# Controller.net
KiCad netlist of a schematic drawn in EAGLE
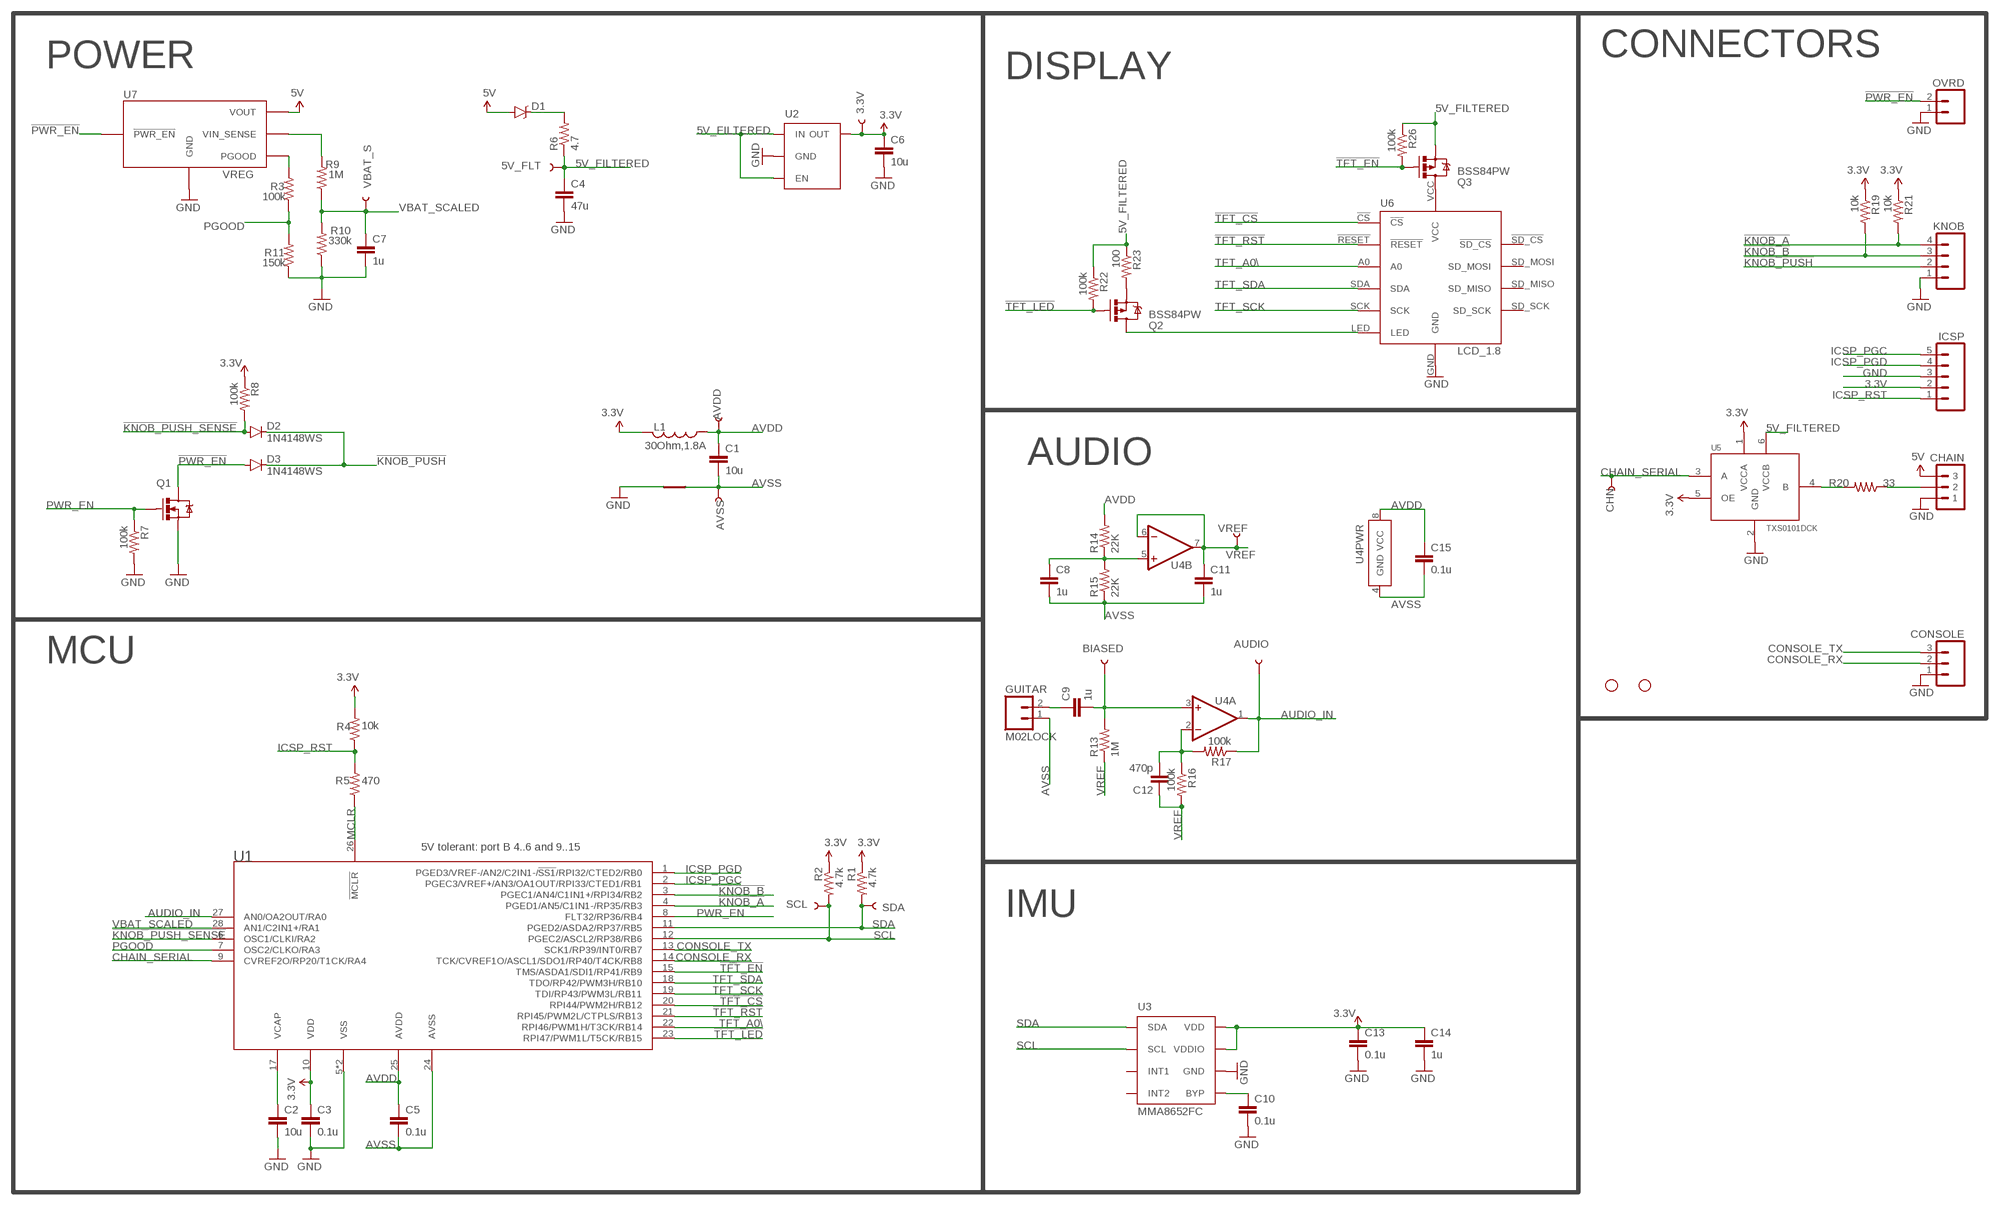
[diagram p0: schematic, sheet 1]

(export (version "E")
  (design (tool "Eeschema 10.0.6"))
  (components
    (comp (ref "3.3V")
      (value "TEST-POINT3")
      (footprint "eagle-import:PAD.03X.03")
      (libsource (lib "eagle-import") (part "TEST-POINT3"))
    )
    (comp (ref "5V_FLT")
      (value "TEST-POINT3")
      (footprint "eagle-import:PAD.03X.03")
      (libsource (lib "eagle-import") (part "TEST-POINT3"))
    )
    (comp (ref "AUDIO")
      (value "TEST-POINT3")
      (footprint "eagle-import:PAD.03X.03")
      (libsource (lib "eagle-import") (part "TEST-POINT3"))
    )
    (comp (ref "AVDD")
      (value "TEST-POINT3")
      (footprint "eagle-import:PAD.03X.03")
      (libsource (lib "eagle-import") (part "TEST-POINT3"))
    )
    (comp (ref "AVSS")
      (value "TEST-POINT3")
      (footprint "eagle-import:PAD.03X.03")
      (libsource (lib "eagle-import") (part "TEST-POINT3"))
    )
    (comp (ref "BIASED")
      (value "TEST-POINT3")
      (footprint "eagle-import:PAD.03X.03")
      (libsource (lib "eagle-import") (part "TEST-POINT3"))
    )
    (comp (ref "C1")
      (value "10u")
      (footprint "eagle-import:0805")
      (libsource (lib "eagle-import") (part "CAP0805"))
    )
    (comp (ref "C2")
      (value "10u")
      (footprint "eagle-import:0805")
      (libsource (lib "eagle-import") (part "CAP0805"))
    )
    (comp (ref "C3")
      (value "0.1u")
      (footprint "eagle-import:0603-CAP")
      (libsource (lib "eagle-import") (part "CAP0603-CAP"))
    )
    (comp (ref "C4")
      (value "47u")
      (footprint "eagle-import:1206")
      (libsource (lib "eagle-import") (part "CAP1206"))
    )
    (comp (ref "C5")
      (value "0.1u")
      (footprint "eagle-import:0603-CAP")
      (libsource (lib "eagle-import") (part "CAP0603-CAP"))
    )
    (comp (ref "C6")
      (value "10u")
      (footprint "eagle-import:0603-CAP")
      (libsource (lib "eagle-import") (part "10UF-6.3V-20%(0603)"))
    )
    (comp (ref "C7")
      (value "1u")
      (footprint "eagle-import:0603-CAP")
      (libsource (lib "eagle-import") (part "CAP0603-CAP"))
    )
    (comp (ref "C8")
      (value "1u")
      (footprint "eagle-import:0603-CAP")
      (libsource (lib "eagle-import") (part "CAP0603-CAP"))
    )
    (comp (ref "C9")
      (value "1u")
      (footprint "eagle-import:0603-CAP")
      (libsource (lib "eagle-import") (part "CAP0603-CAP"))
    )
    (comp (ref "C10")
      (value "0.1u")
      (footprint "eagle-import:0603-CAP")
      (libsource (lib "eagle-import") (part "CAP0603-CAP"))
    )
    (comp (ref "C11")
      (value "1u")
      (footprint "eagle-import:0603-CAP")
      (libsource (lib "eagle-import") (part "CAP0603-CAP"))
    )
    (comp (ref "C12")
      (value "470p")
      (footprint "eagle-import:0603-CAP")
      (libsource (lib "eagle-import") (part "CAP0603-CAP"))
    )
    (comp (ref "C13")
      (value "0.1u")
      (footprint "eagle-import:0603-CAP")
      (libsource (lib "eagle-import") (part "CAP0603-CAP"))
    )
    (comp (ref "C14")
      (value "1u")
      (footprint "eagle-import:0603-CAP")
      (libsource (lib "eagle-import") (part "CAP0603-CAP"))
    )
    (comp (ref "C15")
      (value "0.1u")
      (footprint "eagle-import:0603-CAP")
      (libsource (lib "eagle-import") (part "CAP0603-CAP"))
    )
    (comp (ref "CHAIN")
      (value "M030.1PWR+SIG")
      (footprint "eagle-import:1X03-0.1PWR+SIG")
      (libsource (lib "eagle-import") (part "M030.1PWR+SIG"))
    )
    (comp (ref "CHN")
      (value "TEST-POINT3")
      (footprint "eagle-import:PAD.03X.03")
      (libsource (lib "eagle-import") (part "TEST-POINT3"))
    )
    (comp (ref "CONSOLE")
      (value "M03LOCK")
      (footprint "eagle-import:1X03_LOCK")
      (libsource (lib "eagle-import") (part "SparkFun-Connectors_M03LOCK"))
    )
    (comp (ref "D1")
      (value "DB2J20900L")
      (footprint "eagle-import:SOD-323")
      (libsource (lib "eagle-import") (part "DIODE-SCHOTTKY-PMEG4005EJ"))
    )
    (comp (ref "D2")
      (value "1N4148WS")
      (footprint "eagle-import:SOD-323")
      (libsource (lib "eagle-import") (part "1N4148WS"))
    )
    (comp (ref "D3")
      (value "1N4148WS")
      (footprint "eagle-import:SOD-323")
      (libsource (lib "eagle-import") (part "1N4148WS"))
    )
    (comp (ref "GUITAR")
      (value "M02LOCK")
      (footprint "eagle-import:1X02_LOCK")
      (libsource (lib "eagle-import") (part "M02LOCK"))
    )
    (comp (ref "ICSP")
      (value "M05LOCK")
      (footprint "eagle-import:1X05_LOCK")
      (libsource (lib "eagle-import") (part "M05LOCK"))
    )
    (comp (ref "JP1")
      (value "STAND-OFF")
      (footprint "eagle-import:STAND-OFF")
      (libsource (lib "eagle-import") (part "STAND-OFF"))
    )
    (comp (ref "JP2")
      (value "STAND-OFF")
      (footprint "eagle-import:STAND-OFF")
      (libsource (lib "eagle-import") (part "STAND-OFF"))
    )
    (comp (ref "KNOB")
      (value "M04LOCK")
      (footprint "eagle-import:1X04_LOCK")
      (libsource (lib "eagle-import") (part "M04LOCK"))
    )
    (comp (ref "L1")
      (value "30Ohm,1.8A")
      (footprint "eagle-import:0603")
      (libsource (lib "eagle-import") (part "INDUCTOR0603"))
    )
    (comp (ref "OVRD")
      (value "M02LOCK")
      (footprint "eagle-import:1X02_LOCK")
      (libsource (lib "eagle-import") (part "M02LOCK"))
    )
    (comp (ref "Q1")
      (value "MOSFET-NCHANNEL2N7002PW")
      (footprint "eagle-import:SOT323")
      (libsource (lib "eagle-import") (part "MOSFET-NCHANNEL2N7002PW"))
    )
    (comp (ref "Q2")
      (value "BSS84PW")
      (footprint "eagle-import:SOT323")
      (libsource (lib "eagle-import") (part "BSS84PW"))
    )
    (comp (ref "Q3")
      (value "BSS84PW")
      (footprint "eagle-import:SOT323")
      (libsource (lib "eagle-import") (part "BSS84PW"))
    )
    (comp (ref "R1")
      (value "4.7k")
      (footprint "eagle-import:0603-RES")
      (libsource (lib "eagle-import") (part "RESISTOR0603"))
    )
    (comp (ref "R2")
      (value "4.7k")
      (footprint "eagle-import:0603-RES")
      (libsource (lib "eagle-import") (part "RESISTOR0603"))
    )
    (comp (ref "R3")
      (value "100k")
      (footprint "eagle-import:0603-RES")
      (libsource (lib "eagle-import") (part "RESISTOR0603"))
    )
    (comp (ref "R4")
      (value "10k")
      (footprint "eagle-import:0603-RES")
      (libsource (lib "eagle-import") (part "RESISTOR0603"))
    )
    (comp (ref "R5")
      (value "470")
      (footprint "eagle-import:0603-RES")
      (libsource (lib "eagle-import") (part "RESISTOR0603"))
    )
    (comp (ref "R6")
      (value "4.7")
      (footprint "eagle-import:0603-RES")
      (libsource (lib "eagle-import") (part "RESISTOR0603"))
    )
    (comp (ref "R7")
      (value "100k")
      (footprint "eagle-import:0603-RES")
      (libsource (lib "eagle-import") (part "RESISTOR0603"))
    )
    (comp (ref "R8")
      (value "100k")
      (footprint "eagle-import:0603-RES")
      (libsource (lib "eagle-import") (part "RESISTOR0603"))
    )
    (comp (ref "R9")
      (value "1M")
      (footprint "eagle-import:0603-RES")
      (libsource (lib "eagle-import") (part "RESISTOR0603"))
    )
    (comp (ref "R10")
      (value "330k")
      (footprint "eagle-import:0603-RES")
      (libsource (lib "eagle-import") (part "RESISTOR0603"))
    )
    (comp (ref "R11")
      (value "150k")
      (footprint "eagle-import:0603-RES")
      (libsource (lib "eagle-import") (part "RESISTOR0603"))
    )
    (comp (ref "R13")
      (value "1M")
      (footprint "eagle-import:0603-RES")
      (libsource (lib "eagle-import") (part "RESISTOR0603"))
    )
    (comp (ref "R14")
      (value "22K")
      (footprint "eagle-import:0603-RES")
      (libsource (lib "eagle-import") (part "RESISTOR0603"))
    )
    (comp (ref "R15")
      (value "22K")
      (footprint "eagle-import:0603-RES")
      (libsource (lib "eagle-import") (part "RESISTOR0603"))
    )
    (comp (ref "R16")
      (value "100k")
      (footprint "eagle-import:0603-RES")
      (libsource (lib "eagle-import") (part "RESISTOR0603"))
    )
    (comp (ref "R17")
      (value "100k")
      (footprint "eagle-import:0603-RES")
      (libsource (lib "eagle-import") (part "RESISTOR0603"))
    )
    (comp (ref "R19")
      (value "10k")
      (footprint "eagle-import:0603-RES")
      (libsource (lib "eagle-import") (part "RESISTOR0603"))
    )
    (comp (ref "R20")
      (value "33")
      (footprint "eagle-import:0603-RES")
      (libsource (lib "eagle-import") (part "RESISTOR0603"))
    )
    (comp (ref "R21")
      (value "10k")
      (footprint "eagle-import:0603-RES")
      (libsource (lib "eagle-import") (part "RESISTOR0603"))
    )
    (comp (ref "R22")
      (value "100k")
      (footprint "eagle-import:0603-RES")
      (libsource (lib "eagle-import") (part "RESISTOR0603"))
    )
    (comp (ref "R23")
      (value "100")
      (footprint "eagle-import:0603-RES")
      (libsource (lib "eagle-import") (part "RESISTOR0603"))
    )
    (comp (ref "R26")
      (value "100k")
      (footprint "eagle-import:0603-RES")
      (libsource (lib "eagle-import") (part "RESISTOR0603"))
    )
    (comp (ref "SCL")
      (value "TEST-POINT3")
      (footprint "eagle-import:PAD.03X.03")
      (libsource (lib "eagle-import") (part "TEST-POINT3"))
    )
    (comp (ref "SDA")
      (value "TEST-POINT3")
      (footprint "eagle-import:PAD.03X.03")
      (libsource (lib "eagle-import") (part "TEST-POINT3"))
    )
    (comp (ref "SH1")
      (value "SHORT")
      (footprint "eagle-import:SHORT_TOP-8")
      (libsource (lib "eagle-import") (part "SHORT"))
    )
    (comp (ref "U1")
      (value "DSPIC33EPXXXMC202/502/PT")
      (footprint "eagle-import:QFN-S-28")
      (libsource (lib "eagle-import") (part "DSPIC33EPXXXMC202/502/PT"))
    )
    (comp (ref "U2")
      (value "MIC5365YC5")
      (footprint "eagle-import:SC70")
      (libsource (lib "eagle-import") (part "MIC5365YC5"))
    )
    (comp (ref "U3")
      (value "MMA8652FC")
      (footprint "eagle-import:10-VFDFN")
      (libsource (lib "eagle-import") (part "MMA8652FC"))
    )
    (comp (ref "U4")
      (value "MCP6002MS")
      (footprint "eagle-import:MSOP-8")
      (libsource (lib "eagle-import") (part "MCP6002MS"))
    )
    (comp (ref "U5")
      (value "TXS0101DCK")
      (footprint "eagle-import:SC70-6")
      (libsource (lib "eagle-import") (part "TXS0101DCK"))
    )
    (comp (ref "U6")
      (value "LCD_1.8")
      (footprint "eagle-import:LCD_1.8")
      (libsource (lib "eagle-import") (part "LCD_1.8"))
    )
    (comp (ref "U7")
      (value "VREG")
      (footprint "eagle-import:VREG")
      (libsource (lib "eagle-import") (part "VREG"))
    )
    (comp (ref "VBAT_S")
      (value "TEST-POINT3")
      (footprint "eagle-import:PAD.03X.03")
      (libsource (lib "eagle-import") (part "TEST-POINT3"))
    )
    (comp (ref "VREF")
      (value "TEST-POINT3")
      (footprint "eagle-import:PAD.03X.03")
      (libsource (lib "eagle-import") (part "TEST-POINT3"))
    )
  )
  (nets
    (net (code "1") (name "/5V_FILTERED") (class "Default")
      (node (ref "5V_FLT") (pin "P$1") (pinfunction "1_P$1") (pintype "bidirectional"))
      (node (ref "C4") (pin "1") (pinfunction "1_1") (pintype "passive"))
      (node (ref "Q3") (pin "2") (pinfunction "S_2") (pintype "passive"))
      (node (ref "R22") (pin "1") (pinfunction "1_1") (pintype "passive"))
      (node (ref "R23") (pin "1") (pinfunction "1_1") (pintype "passive"))
      (node (ref "R26") (pin "1") (pinfunction "1_1") (pintype "passive"))
      (node (ref "R6") (pin "1") (pinfunction "1_1") (pintype "passive"))
      (node (ref "U2") (pin "1") (pinfunction "IN_1") (pintype "power_in"))
      (node (ref "U2") (pin "3") (pinfunction "EN_3") (pintype "input"))
      (node (ref "U5") (pin "6") (pinfunction "VCCB_6") (pintype "bidirectional"))
    )
    (net (code "2") (name "/AUDIO_IN") (class "Default")
      (node (ref "AUDIO") (pin "P$1") (pinfunction "1_P$1") (pintype "bidirectional"))
      (node (ref "R17") (pin "1") (pinfunction "1_1") (pintype "passive"))
      (node (ref "U1") (pin "27") (pinfunction "AN0/OA2OUT/RA0_27") (pintype "bidirectional"))
      (node (ref "U4") (pin "1") (pinfunction "OUT_1") (pintype "output"))
    )
    (net (code "3") (name "/AVDD") (class "Default")
      (node (ref "AVDD") (pin "P$1") (pinfunction "1_P$1") (pintype "bidirectional"))
      (node (ref "C1") (pin "1") (pinfunction "1_1") (pintype "passive"))
      (node (ref "C15") (pin "1") (pinfunction "1_1") (pintype "passive"))
      (node (ref "C5") (pin "1") (pinfunction "1_1") (pintype "passive"))
      (node (ref "L1") (pin "1") (pinfunction "1_1") (pintype "passive"))
      (node (ref "R14") (pin "2") (pinfunction "2_2") (pintype "passive"))
      (node (ref "U1") (pin "25") (pinfunction "AVDD_25") (pintype "bidirectional"))
      (node (ref "U4") (pin "8") (pinfunction "VCC_8") (pintype "power_in"))
    )
    (net (code "4") (name "/AVSS") (class "Default")
      (node (ref "AVSS") (pin "P$1") (pinfunction "1_P$1") (pintype "bidirectional"))
      (node (ref "C1") (pin "2") (pinfunction "2_2") (pintype "passive"))
      (node (ref "C11") (pin "2") (pinfunction "2_2") (pintype "passive"))
      (node (ref "C15") (pin "2") (pinfunction "2_2") (pintype "passive"))
      (node (ref "C5") (pin "2") (pinfunction "2_2") (pintype "passive"))
      (node (ref "C8") (pin "2") (pinfunction "2_2") (pintype "passive"))
      (node (ref "GUITAR") (pin "1") (pinfunction "1_1") (pintype "passive"))
      (node (ref "R15") (pin "1") (pinfunction "1_1") (pintype "passive"))
      (node (ref "SH1") (pin "2") (pinfunction "P$2_2") (pintype "bidirectional"))
      (node (ref "U1") (pin "24") (pinfunction "AVSS_24") (pintype "bidirectional"))
      (node (ref "U4") (pin "4") (pinfunction "GND_4") (pintype "power_in"))
    )
    (net (code "5") (name "/CHAIN_SERIAL") (class "Default")
      (node (ref "CHN") (pin "P$1") (pinfunction "1_P$1") (pintype "bidirectional"))
      (node (ref "U1") (pin "9") (pinfunction "CVREF2O/RP20/T1CK/RA4_9") (pintype "bidirectional"))
      (node (ref "U5") (pin "3") (pinfunction "A_3") (pintype "bidirectional"))
    )
    (net (code "6") (name "/CONSOLE_RX") (class "Default")
      (node (ref "CONSOLE") (pin "2") (pinfunction "2_2") (pintype "passive"))
      (node (ref "U1") (pin "14") (pinfunction "TCK/CVREF1O/ASCL1/SDO1/RP40/T4CK/RB8_14") (pintype "bidirectional"))
    )
    (net (code "7") (name "/CONSOLE_TX") (class "Default")
      (node (ref "CONSOLE") (pin "3") (pinfunction "3_3") (pintype "passive"))
      (node (ref "U1") (pin "13") (pinfunction "SCK1/RP39/INT0/RB7_13") (pintype "bidirectional"))
    )
    (net (code "8") (name "/ICSP_PGC") (class "Default")
      (node (ref "ICSP") (pin "5") (pinfunction "5_5") (pintype "passive"))
      (node (ref "U1") (pin "2") (pinfunction "PGEC3/VREF+/AN3/OA1OUT/RPI33/CTED1/RB1_2") (pintype "bidirectional"))
    )
    (net (code "9") (name "/ICSP_PGD") (class "Default")
      (node (ref "ICSP") (pin "4") (pinfunction "4_4") (pintype "passive"))
      (node (ref "U1") (pin "1") (pinfunction "PGED3/VREF-/AN2/C2IN1-/~{SS1}/RPI32/CTED2/RB0_1") (pintype "bidirectional"))
    )
    (net (code "10") (name "/ICSP_RST") (class "Default")
      (node (ref "ICSP") (pin "1") (pinfunction "1_1") (pintype "passive"))
      (node (ref "R4") (pin "1") (pinfunction "1_1") (pintype "passive"))
      (node (ref "R5") (pin "2") (pinfunction "2_2") (pintype "passive"))
    )
    (net (code "11") (name "/MCLR") (class "Default")
      (node (ref "R5") (pin "1") (pinfunction "1_1") (pintype "passive"))
      (node (ref "U1") (pin "26") (pinfunction "~{MCLR}_26") (pintype "bidirectional"))
    )
    (net (code "12") (name "/PGOOD") (class "Default")
      (node (ref "R11") (pin "2") (pinfunction "2_2") (pintype "passive"))
      (node (ref "R3") (pin "1") (pinfunction "1_1") (pintype "passive"))
      (node (ref "U1") (pin "7") (pinfunction "OSC2/CLKO/RA3_7") (pintype "bidirectional"))
    )
    (net (code "13") (name "/PWR_EN") (class "Default")
      (node (ref "Q1") (pin "1") (pinfunction "G_1") (pintype "passive"))
      (node (ref "R7") (pin "1") (pinfunction "1_1") (pintype "passive"))
      (node (ref "U1") (pin "8") (pinfunction "FLT32/RP36/RB4_8") (pintype "bidirectional"))
    )
    (net (code "14") (name "/SCL") (class "Default")
      (node (ref "R2") (pin "2") (pinfunction "2_2") (pintype "passive"))
      (node (ref "SCL") (pin "P$1") (pinfunction "1_P$1") (pintype "bidirectional"))
      (node (ref "U1") (pin "12") (pinfunction "PGEC2/ASCL2/RP38/RB6_12") (pintype "bidirectional"))
      (node (ref "U3") (pin "2") (pinfunction "SCL_2") (pintype "bidirectional"))
    )
    (net (code "15") (name "/SDA") (class "Default")
      (node (ref "R1") (pin "2") (pinfunction "2_2") (pintype "passive"))
      (node (ref "SDA") (pin "P$1") (pinfunction "1_P$1") (pintype "bidirectional"))
      (node (ref "U1") (pin "11") (pinfunction "PGED2/ASDA2/RP37/RB5_11") (pintype "bidirectional"))
      (node (ref "U3") (pin "10") (pinfunction "SDA_10") (pintype "bidirectional"))
    )
    (net (code "16") (name "/TFT_A0\\") (class "Default")
      (node (ref "U1") (pin "22") (pinfunction "RPI46/PWM1H/T3CK/RB14_22") (pintype "bidirectional"))
      (node (ref "U6") (pin "A0") (pinfunction "A0_A0") (pintype "bidirectional"))
    )
    (net (code "17") (name "/TFT_SCK") (class "Default")
      (node (ref "U1") (pin "19") (pinfunction "TDI/RP43/PWM3L/RB11_19") (pintype "bidirectional"))
      (node (ref "U6") (pin "SCK") (pinfunction "SCK_SCK") (pintype "bidirectional"))
    )
    (net (code "18") (name "/TFT_SDA") (class "Default")
      (node (ref "U1") (pin "18") (pinfunction "TDO/RP42/PWM3H/RB10_18") (pintype "bidirectional"))
      (node (ref "U6") (pin "SDA") (pinfunction "SDA_SDA") (pintype "bidirectional"))
    )
    (net (code "19") (name "/VBAT_SCALED") (class "Default")
      (node (ref "C7") (pin "1") (pinfunction "1_1") (pintype "passive"))
      (node (ref "R10") (pin "2") (pinfunction "2_2") (pintype "passive"))
      (node (ref "R9") (pin "1") (pinfunction "1_1") (pintype "passive"))
      (node (ref "U1") (pin "28") (pinfunction "AN1/C2IN1+/RA1_28") (pintype "bidirectional"))
      (node (ref "VBAT_S") (pin "P$1") (pinfunction "1_P$1") (pintype "bidirectional"))
    )
    (net (code "20") (name "/VREF") (class "Default")
      (node (ref "C11") (pin "1") (pinfunction "1_1") (pintype "passive"))
      (node (ref "C12") (pin "1") (pinfunction "1_1") (pintype "passive"))
      (node (ref "R13") (pin "1") (pinfunction "1_1") (pintype "passive"))
      (node (ref "R16") (pin "2") (pinfunction "2_2") (pintype "passive"))
      (node (ref "U4") (pin "6") (pinfunction "-IN_6") (pintype "input"))
      (node (ref "U4") (pin "7") (pinfunction "OUT_7") (pintype "output"))
      (node (ref "VREF") (pin "P$1") (pinfunction "1_P$1") (pintype "bidirectional"))
    )
    (net (code "21") (name "/~{KNOB_A}") (class "Default")
      (node (ref "KNOB") (pin "4") (pinfunction "4_4") (pintype "passive"))
      (node (ref "R21") (pin "2") (pinfunction "2_2") (pintype "passive"))
      (node (ref "U1") (pin "4") (pinfunction "PGED1/AN5/C1IN1-/RP35/RB3_4") (pintype "bidirectional"))
    )
    (net (code "22") (name "/~{KNOB_B}") (class "Default")
      (node (ref "KNOB") (pin "3") (pinfunction "3_3") (pintype "passive"))
      (node (ref "R19") (pin "2") (pinfunction "2_2") (pintype "passive"))
      (node (ref "U1") (pin "3") (pinfunction "PGEC1/AN4/C1IN1+/RPI34/RB2_3") (pintype "bidirectional"))
    )
    (net (code "23") (name "/~{KNOB_PUSH_SENSE}") (class "Default")
      (node (ref "D2") (pin "A") (pinfunction "A_A") (pintype "passive"))
      (node (ref "R8") (pin "2") (pinfunction "2_2") (pintype "passive"))
      (node (ref "U1") (pin "6") (pinfunction "OSC1/CLKI/RA2_6") (pintype "bidirectional"))
    )
    (net (code "24") (name "/~{KNOB_PUSH}") (class "Default")
      (node (ref "D2") (pin "C") (pinfunction "C_C") (pintype "passive"))
      (node (ref "D3") (pin "C") (pinfunction "C_C") (pintype "passive"))
      (node (ref "KNOB") (pin "2") (pinfunction "2_2") (pintype "passive"))
    )
    (net (code "25") (name "/~{PWR_EN}") (class "Default")
      (node (ref "D3") (pin "A") (pinfunction "A_A") (pintype "passive"))
      (node (ref "OVRD") (pin "2") (pinfunction "2_2") (pintype "passive"))
      (node (ref "Q1") (pin "3") (pinfunction "D_3") (pintype "passive"))
      (node (ref "U7") (pin "!EN") (pinfunction "~{PWR_EN}_!EN") (pintype "bidirectional"))
    )
    (net (code "26") (name "/~{TFT_CS}") (class "Default")
      (node (ref "U1") (pin "20") (pinfunction "RPI44/PWM2H/RB12_20") (pintype "bidirectional"))
      (node (ref "U6") (pin "!CS") (pinfunction "~{CS}_!CS") (pintype "bidirectional"))
    )
    (net (code "27") (name "/~{TFT_EN}") (class "Default")
      (node (ref "Q3") (pin "1") (pinfunction "G_1") (pintype "passive"))
      (node (ref "R26") (pin "2") (pinfunction "2_2") (pintype "passive"))
      (node (ref "U1") (pin "15") (pinfunction "TMS/ASDA1/SDI1/RP41/RB9_15") (pintype "bidirectional"))
    )
    (net (code "28") (name "/~{TFT_LED}") (class "Default")
      (node (ref "Q2") (pin "1") (pinfunction "G_1") (pintype "passive"))
      (node (ref "R22") (pin "2") (pinfunction "2_2") (pintype "passive"))
      (node (ref "U1") (pin "23") (pinfunction "RPI47/PWM1L/T5CK/RB15_23") (pintype "bidirectional"))
    )
    (net (code "29") (name "/~{TFT_RST}") (class "Default")
      (node (ref "U1") (pin "21") (pinfunction "RPI45/PWM2L/CTPLS/RB13_21") (pintype "bidirectional"))
      (node (ref "U6") (pin "!RESET") (pinfunction "~{RESET}_!RESET") (pintype "bidirectional"))
    )
    (net (code "30") (name "3.3V") (class "Default")
      (node (ref "3.3V") (pin "P$1") (pinfunction "1_P$1") (pintype "bidirectional"))
      (node (ref "C13") (pin "1") (pinfunction "1_1") (pintype "passive"))
      (node (ref "C14") (pin "1") (pinfunction "1_1") (pintype "passive"))
      (node (ref "C3") (pin "1") (pinfunction "1_1") (pintype "passive"))
      (node (ref "C6") (pin "1") (pinfunction "1_1") (pintype "passive"))
      (node (ref "ICSP") (pin "2") (pinfunction "2_2") (pintype "passive"))
      (node (ref "L1") (pin "2") (pinfunction "2_2") (pintype "passive"))
      (node (ref "R1") (pin "1") (pinfunction "1_1") (pintype "passive"))
      (node (ref "R19") (pin "1") (pinfunction "1_1") (pintype "passive"))
      (node (ref "R2") (pin "1") (pinfunction "1_1") (pintype "passive"))
      (node (ref "R21") (pin "1") (pinfunction "1_1") (pintype "passive"))
      (node (ref "R4") (pin "2") (pinfunction "2_2") (pintype "passive"))
      (node (ref "R8") (pin "1") (pinfunction "1_1") (pintype "passive"))
      (node (ref "U1") (pin "10") (pinfunction "VDD_10") (pintype "bidirectional"))
      (node (ref "U2") (pin "5") (pinfunction "OUT_5") (pintype "power_in"))
      (node (ref "U3") (pin "1") (pinfunction "VDD_1") (pintype "bidirectional"))
      (node (ref "U3") (pin "8") (pinfunction "VDDIO_8") (pintype "bidirectional"))
      (node (ref "U5") (pin "1") (pinfunction "VCCA_1") (pintype "bidirectional"))
      (node (ref "U5") (pin "5") (pinfunction "OE_5") (pintype "bidirectional"))
    )
    (net (code "31") (name "5V") (class "Default")
      (node (ref "CHAIN") (pin "P$3") (pinfunction "3_P$3") (pintype "passive"))
      (node (ref "D1") (pin "A") (pinfunction "A_A") (pintype "passive"))
      (node (ref "U7") (pin "VOUT") (pinfunction "VOUT_VOUT") (pintype "bidirectional"))
    )
    (net (code "32") (name "GND") (class "Default")
      (node (ref "C10") (pin "2") (pinfunction "2_2") (pintype "passive"))
      (node (ref "C13") (pin "2") (pinfunction "2_2") (pintype "passive"))
      (node (ref "C14") (pin "2") (pinfunction "2_2") (pintype "passive"))
      (node (ref "C2") (pin "2") (pinfunction "2_2") (pintype "passive"))
      (node (ref "C3") (pin "2") (pinfunction "2_2") (pintype "passive"))
      (node (ref "C4") (pin "2") (pinfunction "2_2") (pintype "passive"))
      (node (ref "C6") (pin "2") (pinfunction "2_2") (pintype "passive"))
      (node (ref "C7") (pin "2") (pinfunction "2_2") (pintype "passive"))
      (node (ref "CHAIN") (pin "P$1") (pinfunction "1_P$1") (pintype "passive"))
      (node (ref "CONSOLE") (pin "1") (pinfunction "1_1") (pintype "passive"))
      (node (ref "ICSP") (pin "3") (pinfunction "3_3") (pintype "passive"))
      (node (ref "KNOB") (pin "1") (pinfunction "1_1") (pintype "passive"))
      (node (ref "OVRD") (pin "1") (pinfunction "1_1") (pintype "passive"))
      (node (ref "Q1") (pin "2") (pinfunction "S_2") (pintype "passive"))
      (node (ref "R10") (pin "1") (pinfunction "1_1") (pintype "passive"))
      (node (ref "R11") (pin "1") (pinfunction "1_1") (pintype "passive"))
      (node (ref "R7") (pin "2") (pinfunction "2_2") (pintype "passive"))
      (node (ref "SH1") (pin "1") (pinfunction "P$1_1") (pintype "bidirectional"))
      (node (ref "U1") (pin "16") (pinfunction "VSS_16") (pintype "bidirectional"))
      (node (ref "U1") (pin "5") (pinfunction "VSS_5") (pintype "bidirectional"))
      (node (ref "U2") (pin "2") (pinfunction "GND_2") (pintype "power_in"))
      (node (ref "U3") (pin "6") (pinfunction "GND_6") (pintype "bidirectional"))
      (node (ref "U3") (pin "7") (pinfunction "GND_7") (pintype "bidirectional"))
      (node (ref "U3") (pin "9") (pinfunction "GND_9") (pintype "bidirectional"))
      (node (ref "U5") (pin "2") (pinfunction "GND_2") (pintype "bidirectional"))
      (node (ref "U6") (pin "GND") (pinfunction "GND_GND") (pintype "power_in"))
      (node (ref "U7") (pin "GND_OUT") (pinfunction "GND_GND_OUT") (pintype "bidirectional"))
    )
    (net (code "33") (name "Net-(BIASED-1)") (class "Default")
      (node (ref "BIASED") (pin "P$1") (pinfunction "1_P$1") (pintype "bidirectional"))
      (node (ref "C9") (pin "2") (pinfunction "2_2") (pintype "passive"))
      (node (ref "R13") (pin "2") (pinfunction "2_2") (pintype "passive"))
      (node (ref "U4") (pin "3") (pinfunction "+IN_3") (pintype "input"))
    )
    (net (code "34") (name "Net-(C9-Pad1)") (class "Default")
      (node (ref "C9") (pin "1") (pinfunction "1_1") (pintype "passive"))
      (node (ref "GUITAR") (pin "2") (pinfunction "2_2") (pintype "passive"))
    )
    (net (code "35") (name "Net-(CHAIN-2)") (class "Default")
      (node (ref "CHAIN") (pin "P$2") (pinfunction "2_P$2") (pintype "passive"))
      (node (ref "R20") (pin "1") (pinfunction "1_1") (pintype "passive"))
    )
    (net (code "36") (name "Net-(D1-PadC)") (class "Default")
      (node (ref "D1") (pin "C") (pinfunction "C_C") (pintype "passive"))
      (node (ref "R6") (pin "2") (pinfunction "2_2") (pintype "passive"))
    )
    (net (code "37") (name "Net-(Q2-D)") (class "Default")
      (node (ref "Q2") (pin "3") (pinfunction "D_3") (pintype "passive"))
      (node (ref "U6") (pin "LED") (pinfunction "LED_LED") (pintype "bidirectional"))
    )
    (net (code "38") (name "Net-(Q2-S)") (class "Default")
      (node (ref "Q2") (pin "2") (pinfunction "S_2") (pintype "passive"))
      (node (ref "R23") (pin "2") (pinfunction "2_2") (pintype "passive"))
    )
    (net (code "39") (name "Net-(Q3-D)") (class "Default")
      (node (ref "Q3") (pin "3") (pinfunction "D_3") (pintype "passive"))
      (node (ref "U6") (pin "VCC") (pinfunction "VCC_VCC") (pintype "power_in"))
    )
    (net (code "40") (name "Net-(R3-Pad2)") (class "Default")
      (node (ref "R3") (pin "2") (pinfunction "2_2") (pintype "passive"))
      (node (ref "U7") (pin "PGOOD") (pinfunction "PGOOD_PGOOD") (pintype "bidirectional"))
    )
    (net (code "41") (name "Net-(U1-VCAP)") (class "Default")
      (node (ref "C2") (pin "1") (pinfunction "1_1") (pintype "passive"))
      (node (ref "U1") (pin "17") (pinfunction "VCAP_17") (pintype "bidirectional"))
    )
    (net (code "42") (name "Net-(U3-BYP)") (class "Default")
      (node (ref "C10") (pin "1") (pinfunction "1_1") (pintype "passive"))
      (node (ref "U3") (pin "4") (pinfunction "BYP_4") (pintype "bidirectional"))
    )
    (net (code "43") (name "Net-(U4A--IN)") (class "Default")
      (node (ref "C12") (pin "2") (pinfunction "2_2") (pintype "passive"))
      (node (ref "R16") (pin "1") (pinfunction "1_1") (pintype "passive"))
      (node (ref "R17") (pin "2") (pinfunction "2_2") (pintype "passive"))
      (node (ref "U4") (pin "2") (pinfunction "-IN_2") (pintype "input"))
    )
    (net (code "44") (name "Net-(U4B-+IN)") (class "Default")
      (node (ref "C8") (pin "1") (pinfunction "1_1") (pintype "passive"))
      (node (ref "R14") (pin "1") (pinfunction "1_1") (pintype "passive"))
      (node (ref "R15") (pin "2") (pinfunction "2_2") (pintype "passive"))
      (node (ref "U4") (pin "5") (pinfunction "+IN_5") (pintype "input"))
    )
    (net (code "45") (name "Net-(U5-B)") (class "Default")
      (node (ref "R20") (pin "2") (pinfunction "2_2") (pintype "passive"))
      (node (ref "U5") (pin "4") (pinfunction "B_4") (pintype "bidirectional"))
    )
    (net (code "46") (name "Net-(U7-VIN_SENSE)") (class "Default")
      (node (ref "R9") (pin "2") (pinfunction "2_2") (pintype "passive"))
      (node (ref "U7") (pin "VSENSE") (pinfunction "VIN_SENSE_VSENSE") (pintype "bidirectional"))
    )
    (net (code "47") (name "unconnected-(U3-INT1-Pad3)") (class "Default")
      (node (ref "U3") (pin "3") (pinfunction "INT1_3") (pintype "bidirectional"))
    )
    (net (code "48") (name "unconnected-(U3-INT2-Pad5)") (class "Default")
      (node (ref "U3") (pin "5") (pinfunction "INT2_5") (pintype "bidirectional"))
    )
    (net (code "49") (name "unconnected-(U6-PadSD_MISO)") (class "Default")
      (node (ref "U6") (pin "SD_MISO") (pinfunction "SD_MISO_SD_MISO") (pintype "bidirectional"))
    )
    (net (code "50") (name "unconnected-(U6-PadSD_MOSI)") (class "Default")
      (node (ref "U6") (pin "SD_MOSI") (pinfunction "SD_MOSI_SD_MOSI") (pintype "bidirectional"))
    )
    (net (code "51") (name "unconnected-(U6-PadSD_SCK)") (class "Default")
      (node (ref "U6") (pin "SD_SCK") (pinfunction "SD_SCK_SD_SCK") (pintype "bidirectional"))
    )
    (net (code "52") (name "unconnected-(U6-~{SD_CS}-Pad!SD_CS)") (class "Default")
      (node (ref "U6") (pin "!SD_CS") (pinfunction "~{SD_CS}_!SD_CS") (pintype "bidirectional"))
    )
  )
)
